# ESP_12.net
KiCad netlist of a schematic drawn in Altium Designer
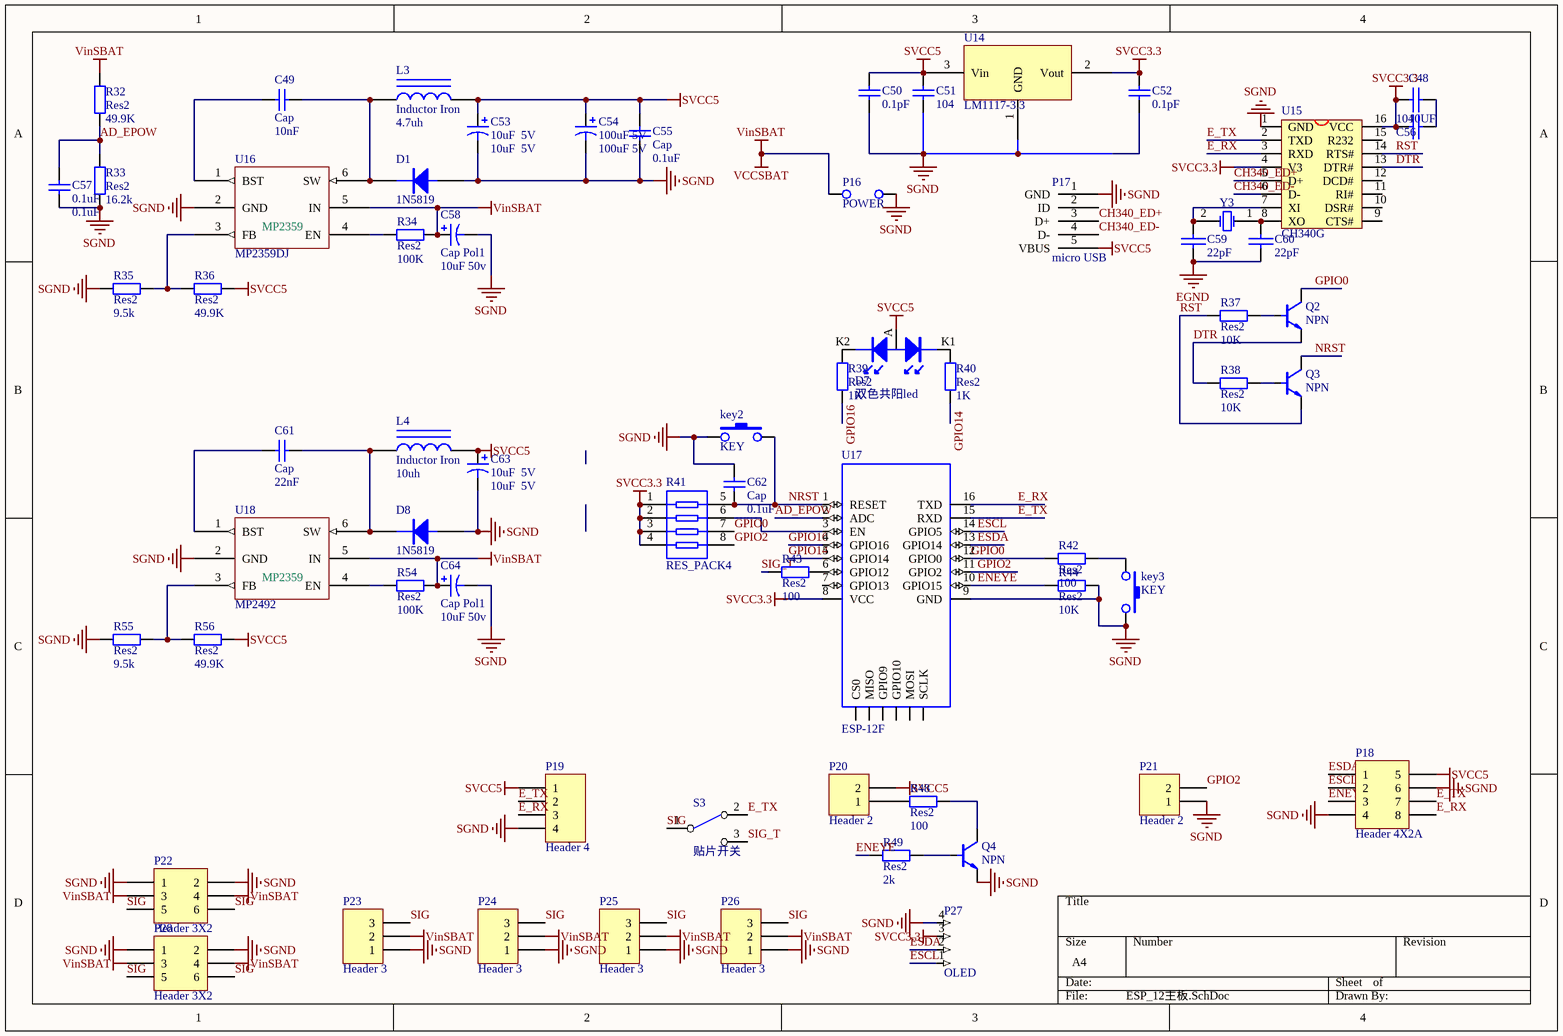
[diagram p0: ESP_12主板.SchDoc]

(export (version "E")
  (design (tool "Eeschema 10.0.6"))
  (components
    (comp (ref "C48")
      (value "10UF")
      (footprint "LC-0603_C")
      (fields (field (name "Comment") "CAP"))
      (libsource (lib "MySchLib") (part "CAP"))
    )
    (comp (ref "C49")
      (value "Cap")
      (footprint "LC-0603_C")
      (description "Capacitor")
      (fields (field (name "ALTIUM_VALUE") "10nF") (field (name "PUBLISHER") "Altium Limited"))
      (libsource (lib "Miscellaneous Devices") (part "Cap"))
    )
    (comp (ref "C50")
      (value "0.1pF")
      (footprint "LC-0603_C")
      (description "Capacitor")
      (fields (field (name "Comment") "Cap") (field (name "PUBLISHER") "Altium Limited"))
      (libsource (lib "Miscellaneous Devices") (part "Cap"))
    )
    (comp (ref "C51")
      (value "104")
      (footprint "LC-Standard-FootPrints-AD-V1.00:LC-1210_C")
      (description "Capacitor")
      (fields (field (name "Comment") "Cap") (field (name "PUBLISHER") "Altium Limited"))
      (libsource (lib "Miscellaneous Devices") (part "Cap"))
    )
    (comp (ref "C52")
      (value "0.1pF")
      (footprint "LC-0603_C")
      (description "Capacitor")
      (fields (field (name "Comment") "Cap") (field (name "PUBLISHER") "Altium Limited"))
      (libsource (lib "Miscellaneous Devices") (part "Cap"))
    )
    (comp (ref "C53")
      (value "10uF  5V")
      (footprint "LC-1210_C")
      (description "Polarized Capacitor (Radial)")
      (fields (field (name "ALTIUM_VALUE") "10uF  5V") (field (name "PUBLISHER") "Altium Limited"))
      (libsource (lib "Miscellaneous Devices") (part "Cap Pol1"))
    )
    (comp (ref "C54")
      (value "100uF 5V")
      (footprint "电容HONOR_63X77")
      (description "Polarized Capacitor (Radial)")
      (fields (field (name "ALTIUM_VALUE") "100uF 5V") (field (name "PUBLISHER") "Altium Limited"))
      (libsource (lib "Miscellaneous Devices") (part "Cap Pol1"))
    )
    (comp (ref "C55")
      (value "Cap")
      (footprint "LC-0603_C")
      (description "Capacitor")
      (fields (field (name "ALTIUM_VALUE") "0.1uF") (field (name "PUBLISHER") "Altium Limited"))
      (libsource (lib "Miscellaneous Devices") (part "Cap"))
    )
    (comp (ref "C56")
      (value "104")
      (footprint "LC-1206_C")
      (fields (field (name "Comment") "CAP"))
      (libsource (lib "MySchLib") (part "CAP"))
    )
    (comp (ref "C57")
      (value "0.1uF")
      (footprint "LC-0603_C")
      (description "Capacitor")
      (fields (field (name "ALTIUM_VALUE") "0.1uF") (field (name "PUBLISHER") "Altium Limited"))
      (libsource (lib "Miscellaneous Devices") (part "Cap"))
    )
    (comp (ref "C58")
      (value "Cap Pol1")
      (footprint "电容HONOR_63X54")
      (description "Polarized Capacitor (Radial)")
      (fields (field (name "ALTIUM_VALUE") "10uF 50v") (field (name "PUBLISHER") "Altium Limited"))
      (libsource (lib "Miscellaneous Devices") (part "Cap Pol1"))
    )
    (comp (ref "C59")
      (value "22pF")
      (footprint "LC-0603_C")
      (fields (field (name "Comment") "CAP"))
      (libsource (lib "MySchLib") (part "CAP"))
    )
    (comp (ref "C60")
      (value "22pF")
      (footprint "LC-0603_C")
      (fields (field (name "Comment") "CAP"))
      (libsource (lib "MySchLib") (part "CAP"))
    )
    (comp (ref "C61")
      (value "Cap")
      (footprint "LC-0603_C")
      (description "Capacitor")
      (fields (field (name "ALTIUM_VALUE") "22nF") (field (name "PUBLISHER") "Altium Limited"))
      (libsource (lib "Miscellaneous Devices") (part "Cap"))
    )
    (comp (ref "C62")
      (value "Cap")
      (footprint "LC-0603_C")
      (description "Capacitor")
      (fields (field (name "ALTIUM_VALUE") "0.1uF") (field (name "PUBLISHER") "Altium Limited"))
      (libsource (lib "Miscellaneous Devices") (part "Cap"))
    )
    (comp (ref "C63")
      (value "10uF  5V")
      (footprint "LC-1210_C")
      (description "Polarized Capacitor (Radial)")
      (fields (field (name "ALTIUM_VALUE") "10uF  5V") (field (name "PUBLISHER") "Altium Limited"))
      (libsource (lib "Miscellaneous Devices") (part "Cap Pol1"))
    )
    (comp (ref "C64")
      (value "Cap Pol1")
      (footprint "电容HONOR_63X54")
      (description "Polarized Capacitor (Radial)")
      (fields (field (name "ALTIUM_VALUE") "10uF 50v") (field (name "PUBLISHER") "Altium Limited"))
      (libsource (lib "Miscellaneous Devices") (part "Cap Pol1"))
    )
    (comp (ref "D1") (value "1N5819") (footprint "SMA") (libsource (lib "ARAMYLIB") (part "1N4001")))
    (comp (ref "D7") (value "双色共阳led") (footprint "共阳双色LED") (libsource (lib "ros_car_lib") (part "双色共阳led")))
    (comp (ref "D8") (value "1N5819") (footprint "SMA") (libsource (lib "ARAMYLIB") (part "1N4001")))
    (comp (ref "key2") (value "KEY") (footprint "SMD轻触按键") (libsource (lib "ros_car_lib") (part "KEY")))
    (comp (ref "key3") (value "KEY") (footprint "SMD轻触按键") (libsource (lib "ros_car_lib") (part "KEY")))
    (comp (ref "L3")
      (value "Inductor Iron")
      (footprint "电感GDCD4532")
      (description "Magnetic-Core Inductor")
      (fields (field (name "ALTIUM_VALUE") "4.7uh") (field (name "PUBLISHER") "Altium Limited"))
      (libsource (lib "Miscellaneous Devices") (part "Inductor Iron"))
    )
    (comp (ref "L4")
      (value "Inductor Iron")
      (footprint "电感GDCD4532")
      (description "Magnetic-Core Inductor")
      (fields (field (name "ALTIUM_VALUE") "10uh") (field (name "PUBLISHER") "Altium Limited"))
      (libsource (lib "Miscellaneous Devices") (part "Inductor Iron"))
    )
    (comp (ref "P16") (value "POWER") (footprint "电源") (libsource (lib "ROS_CAR_LIB") (part "POWER")))
    (comp (ref "P17")
      (value "micro USB")
      (footprint "micro 5P沉板式0.8四脚全插无导位有孔")
      (libsource (lib "ROS_CAR_LIB") (part "micro 5P"))
    )
    (comp (ref "P18")
      (value "Header 4X2A")
      (footprint "HDR2X4_CEN")
      (description "Header, 4-Pin, Dual row")
      (fields (field (name "PUBLISHER") "Altium Limited"))
      (libsource (lib "Miscellaneous Connectors") (part "Header 4X2A"))
    )
    (comp (ref "P19")
      (value "Header 4")
      (footprint "HDR1X4")
      (description "Header, 4-Pin")
      (fields (field (name "PUBLISHER") "Altium Limited"))
      (libsource (lib "Miscellaneous Connectors") (part "Header 4"))
    )
    (comp (ref "P20")
      (value "Header 2")
      (footprint "HDR1X2")
      (description "Header, 2-Pin")
      (fields (field (name "PUBLISHER") "Altium Limited"))
      (libsource (lib "Miscellaneous Connectors") (part "Header 2"))
    )
    (comp (ref "P21")
      (value "Header 2")
      (footprint "HDR1X2")
      (description "Header, 2-Pin")
      (fields (field (name "PUBLISHER") "Altium Limited"))
      (libsource (lib "Miscellaneous Connectors") (part "Header 2"))
    )
    (comp (ref "P22")
      (value "Header 3X2")
      (footprint "HDR2X3")
      (description "Header, 3-Pin, Dual row")
      (fields (field (name "PUBLISHER") "Altium Limited"))
      (libsource (lib "Miscellaneous Connectors") (part "Header 3X2"))
    )
    (comp (ref "P23")
      (value "Header 3")
      (footprint "AMP 3针连接件")
      (description "Header, 3-Pin")
      (fields (field (name "PUBLISHER") "Altium Limited"))
      (libsource (lib "Miscellaneous Connectors") (part "Header 3"))
    )
    (comp (ref "P24")
      (value "Header 3")
      (footprint "AMP 3针连接件")
      (description "Header, 3-Pin")
      (fields (field (name "PUBLISHER") "Altium Limited"))
      (libsource (lib "Miscellaneous Connectors") (part "Header 3"))
    )
    (comp (ref "P25")
      (value "Header 3")
      (footprint "AMP 3针连接件")
      (description "Header, 3-Pin")
      (fields (field (name "PUBLISHER") "Altium Limited"))
      (libsource (lib "Miscellaneous Connectors") (part "Header 3"))
    )
    (comp (ref "P26")
      (value "Header 3")
      (footprint "AMP 3针连接件")
      (description "Header, 3-Pin")
      (fields (field (name "PUBLISHER") "Altium Limited"))
      (libsource (lib "Miscellaneous Connectors") (part "Header 3"))
    )
    (comp (ref "P27")
      (value "OLED")
      (footprint "1.0MM 翻盖 下接 FPC连接器 4P")
      (libsource (lib "ros_car_lib") (part "FPC 4P 1MM"))
    )
    (comp (ref "P28")
      (value "Header 3X2")
      (footprint "HDR2X3")
      (description "Header, 3-Pin, Dual row")
      (fields (field (name "PUBLISHER") "Altium Limited"))
      (libsource (lib "Miscellaneous Connectors") (part "Header 3X2"))
    )
    (comp (ref "Q2") (value "NPN") (footprint "LC-SOT-23") (libsource (lib "ARAMYLIB") (part "NPN")))
    (comp (ref "Q3") (value "NPN") (footprint "LC-SOT-23") (libsource (lib "ARAMYLIB") (part "NPN")))
    (comp (ref "Q4") (value "NPN") (footprint "LC-SOT-23") (libsource (lib "ARAMYLIB") (part "NPN")))
    (comp (ref "R32")
      (value "Res2")
      (footprint "LC-0603_R")
      (description "Resistor")
      (fields (field (name "ALTIUM_VALUE") "49.9K") (field (name "PUBLISHER") "Altium Limited"))
      (libsource (lib "") (part "Res2_2"))
    )
    (comp (ref "R33")
      (value "Res2")
      (footprint "LC-0603_R")
      (description "Resistor")
      (fields (field (name "ALTIUM_VALUE") "16.2k") (field (name "PUBLISHER") "Altium Limited"))
      (libsource (lib "") (part "Res2_2"))
    )
    (comp (ref "R34")
      (value "Res2")
      (footprint "LC-0603_R")
      (description "Resistor")
      (fields (field (name "ALTIUM_VALUE") "100K") (field (name "PUBLISHER") "Altium Limited"))
      (libsource (lib "") (part "Res2_1"))
    )
    (comp (ref "R35")
      (value "Res2")
      (footprint "LC-0603_R")
      (description "Resistor")
      (fields (field (name "ALTIUM_VALUE") "9.5k") (field (name "PUBLISHER") "Altium Limited"))
      (libsource (lib "Miscellaneous Devices") (part "Res2"))
    )
    (comp (ref "R36")
      (value "Res2")
      (footprint "LC-0603_R")
      (description "Resistor")
      (fields (field (name "ALTIUM_VALUE") "49.9K") (field (name "PUBLISHER") "Altium Limited"))
      (libsource (lib "Miscellaneous Devices") (part "Res2"))
    )
    (comp (ref "R37")
      (value "Res2")
      (footprint "LC-0603_R")
      (description "Resistor")
      (fields (field (name "ALTIUM_VALUE") "10K") (field (name "PUBLISHER") "Altium Limited"))
      (libsource (lib "") (part "Res2_1"))
    )
    (comp (ref "R38")
      (value "Res2")
      (footprint "LC-0603_R")
      (description "Resistor")
      (fields (field (name "ALTIUM_VALUE") "10K") (field (name "PUBLISHER") "Altium Limited"))
      (libsource (lib "") (part "Res2_1"))
    )
    (comp (ref "R39")
      (value "Res2")
      (footprint "LC-0603_R")
      (description "Resistor")
      (fields (field (name "ALTIUM_VALUE") "1K") (field (name "PUBLISHER") "Altium Limited"))
      (libsource (lib "") (part "Res2_3"))
    )
    (comp (ref "R40")
      (value "Res2")
      (footprint "LC-0603_R")
      (description "Resistor")
      (fields (field (name "ALTIUM_VALUE") "1K") (field (name "PUBLISHER") "Altium Limited"))
      (libsource (lib "") (part "Res2_3"))
    )
    (comp (ref "R41") (value "RES_PACK4") (footprint "RES4") (libsource (lib "ARAMYLIB") (part "RES_PACK4")))
    (comp (ref "R42")
      (value "Res2")
      (footprint "LC-0603_R")
      (description "Resistor")
      (fields (field (name "ALTIUM_VALUE") "100") (field (name "PUBLISHER") "Altium Limited"))
      (libsource (lib "") (part "Res2_1"))
    )
    (comp (ref "R43")
      (value "Res2")
      (footprint "LC-0603_R")
      (description "Resistor")
      (fields (field (name "ALTIUM_VALUE") "100") (field (name "PUBLISHER") "Altium Limited"))
      (libsource (lib "") (part "Res2_1"))
    )
    (comp (ref "R44")
      (value "Res2")
      (footprint "LC-0603_R")
      (description "Resistor")
      (fields (field (name "ALTIUM_VALUE") "10K") (field (name "PUBLISHER") "Altium Limited"))
      (libsource (lib "") (part "Res2_1"))
    )
    (comp (ref "R48")
      (value "Res2")
      (footprint "LC-0603_R")
      (description "Resistor")
      (fields (field (name "ALTIUM_VALUE") "100") (field (name "PUBLISHER") "Altium Limited"))
      (libsource (lib "") (part "Res2_1"))
    )
    (comp (ref "R49")
      (value "Res2")
      (footprint "LC-0603_R")
      (description "Resistor")
      (fields (field (name "ALTIUM_VALUE") "2k") (field (name "PUBLISHER") "Altium Limited"))
      (libsource (lib "Miscellaneous Devices") (part "Res2"))
    )
    (comp (ref "R54")
      (value "Res2")
      (footprint "LC-0603_R")
      (description "Resistor")
      (fields (field (name "ALTIUM_VALUE") "100K") (field (name "PUBLISHER") "Altium Limited"))
      (libsource (lib "") (part "Res2_1"))
    )
    (comp (ref "R55")
      (value "Res2")
      (footprint "LC-0603_R")
      (description "Resistor")
      (fields (field (name "ALTIUM_VALUE") "9.5k") (field (name "PUBLISHER") "Altium Limited"))
      (libsource (lib "Miscellaneous Devices") (part "Res2"))
    )
    (comp (ref "R56")
      (value "Res2")
      (footprint "LC-0603_R")
      (description "Resistor")
      (fields (field (name "ALTIUM_VALUE") "49.9K") (field (name "PUBLISHER") "Altium Limited"))
      (libsource (lib "Miscellaneous Devices") (part "Res2"))
    )
    (comp (ref "S3") (value "贴片开关") (footprint "KEY") (libsource (lib "aramy_四轴") (part "贴片开关")))
    (comp (ref "U14")
      (value "LM1117-3.3")
      (footprint "SOT223")
      (libsource (lib "MySchLib") (part "LM1117-3.3"))
    )
    (comp (ref "U15")
      (value "CH340G")
      (footprint "SOP16M")
      (description "USB2UART")
      (libsource (lib "EliteSTM32封装库") (part "CH340G"))
    )
    (comp (ref "U16")
      (value "MP2359DJ")
      (footprint "LC-SOT-23-6")
      (libsource (lib "ARAMYLIB") (part "MP2359DJ"))
    )
    (comp (ref "U17") (value "ESP-12F") (footprint "ESP_12") (libsource (lib "ros_car_lib") (part "ESP-12F")))
    (comp (ref "U18")
      (value "MP2492")
      (footprint "LC-SOT-23-6")
      (libsource (lib "ARAMYLIB") (part "MP2359DJ"))
    )
    (comp (ref "Y3")
      (value "12MHz")
      (footprint "49SMD")
      (description "Crystal Oscillator")
      (fields (field (name "PUBLISHER") "Altium Limited"))
      (libsource (lib "ALIENTEK_底板封装库") (part "XTAL"))
    )
  )
  (nets
    (net (code "1") (name "/AD_EPOW") (class "Default")
      (node (ref "C57") (pin "1") (pinfunction "1_1") (pintype "passive"))
      (node (ref "R32") (pin "2") (pinfunction "2_2") (pintype "passive"))
      (node (ref "R33") (pin "1") (pinfunction "1_1") (pintype "passive"))
      (node (ref "U17") (pin "2") (pinfunction "ADC_2") (pintype "bidirectional"))
    )
    (net (code "2") (name "/CH340_ED+") (class "Default")
      (node (ref "P17") (pin "3") (pinfunction "D+_3") (pintype "passive"))
      (node (ref "U15") (pin "5") (pinfunction "D+_5") (pintype "passive"))
    )
    (net (code "3") (name "/CH340_ED-") (class "Default")
      (node (ref "P17") (pin "4") (pinfunction "D-_4") (pintype "passive"))
      (node (ref "U15") (pin "6") (pinfunction "D-_6") (pintype "passive"))
    )
    (net (code "4") (name "/DTR") (class "Default")
      (node (ref "Q2") (pin "E") (pinfunction "e_E") (pintype "passive"))
      (node (ref "R38") (pin "1") (pinfunction "1_1") (pintype "passive"))
      (node (ref "U15") (pin "13") (pinfunction "DTR#_13") (pintype "passive"))
    )
    (net (code "5") (name "/ENEYE") (class "Default")
      (node (ref "P18") (pin "3") (pinfunction "3_3") (pintype "passive"))
      (node (ref "R44") (pin "1") (pinfunction "1_1") (pintype "passive"))
      (node (ref "R49") (pin "2") (pinfunction "2_2") (pintype "passive"))
      (node (ref "U17") (pin "10") (pinfunction "GPIO15_10") (pintype "bidirectional"))
    )
    (net (code "6") (name "/ESCL") (class "Default")
      (node (ref "P18") (pin "2") (pinfunction "2_2") (pintype "passive"))
      (node (ref "P27") (pin "1") (pinfunction "1_1") (pintype "input"))
      (node (ref "U17") (pin "14") (pinfunction "GPIO5_14") (pintype "bidirectional"))
    )
    (net (code "7") (name "/ESDA") (class "Default")
      (node (ref "P18") (pin "1") (pinfunction "1_1") (pintype "passive"))
      (node (ref "P27") (pin "2") (pinfunction "2_2") (pintype "input"))
      (node (ref "U17") (pin "13") (pinfunction "GPIO14_13") (pintype "bidirectional"))
    )
    (net (code "8") (name "/E_RX") (class "Default")
      (node (ref "P18") (pin "8") (pinfunction "8_8") (pintype "passive"))
      (node (ref "P19") (pin "3") (pinfunction "3_3") (pintype "passive"))
      (node (ref "U15") (pin "3") (pinfunction "RXD_3") (pintype "passive"))
      (node (ref "U17") (pin "16") (pinfunction "TXD_16") (pintype "passive"))
    )
    (net (code "9") (name "/E_TX") (class "Default")
      (node (ref "P18") (pin "7") (pinfunction "7_7") (pintype "passive"))
      (node (ref "P19") (pin "2") (pinfunction "2_2") (pintype "passive"))
      (node (ref "S3") (pin "2") (pinfunction "NC1_2") (pintype "passive"))
      (node (ref "U15") (pin "2") (pinfunction "TXD_2") (pintype "passive"))
      (node (ref "U17") (pin "15") (pinfunction "RXD_15") (pintype "passive"))
    )
    (net (code "10") (name "/GPIO0") (class "Default")
      (node (ref "Q2") (pin "C") (pinfunction "c_C") (pintype "passive"))
      (node (ref "R41") (pin "7") (pinfunction "7_7") (pintype "passive"))
      (node (ref "R42") (pin "1") (pinfunction "1_1") (pintype "passive"))
      (node (ref "U17") (pin "12") (pinfunction "GPIO0_12") (pintype "bidirectional"))
    )
    (net (code "11") (name "/GPIO2") (class "Default")
      (node (ref "P21") (pin "2") (pinfunction "2_2") (pintype "passive"))
      (node (ref "R41") (pin "8") (pinfunction "8_8") (pintype "passive"))
      (node (ref "U17") (pin "11") (pinfunction "GPIO2_11") (pintype "bidirectional"))
    )
    (net (code "12") (name "/GPIO14") (class "Default")
      (node (ref "R40") (pin "1") (pinfunction "1_1") (pintype "passive"))
      (node (ref "U17") (pin "5") (pinfunction "GPIO14_5") (pintype "bidirectional"))
    )
    (net (code "13") (name "/GPIO16") (class "Default")
      (node (ref "R39") (pin "1") (pinfunction "1_1") (pintype "passive"))
      (node (ref "U17") (pin "4") (pinfunction "GPIO16_4") (pintype "bidirectional"))
    )
    (net (code "14") (name "/NRST") (class "Default")
      (node (ref "C62") (pin "1") (pinfunction "1_1") (pintype "passive"))
      (node (ref "Q3") (pin "C") (pinfunction "c_C") (pintype "passive"))
      (node (ref "R41") (pin "5") (pinfunction "5_5") (pintype "passive"))
      (node (ref "U17") (pin "1") (pinfunction "RESET_1") (pintype "bidirectional"))
      (node (ref "key2") (pin "2") (pinfunction "2_2") (pintype "passive"))
    )
    (net (code "15") (name "/RST") (class "Default")
      (node (ref "Q3") (pin "E") (pinfunction "e_E") (pintype "passive"))
      (node (ref "R37") (pin "1") (pinfunction "1_1") (pintype "passive"))
      (node (ref "U15") (pin "14") (pinfunction "RTS#_14") (pintype "passive"))
    )
    (net (code "16") (name "/SIG") (class "Default")
      (node (ref "P22") (pin "5") (pinfunction "5_5") (pintype "passive"))
      (node (ref "P22") (pin "6") (pinfunction "6_6") (pintype "passive"))
      (node (ref "P23") (pin "3") (pinfunction "3_3") (pintype "passive"))
      (node (ref "P24") (pin "3") (pinfunction "3_3") (pintype "passive"))
      (node (ref "P25") (pin "3") (pinfunction "3_3") (pintype "passive"))
      (node (ref "P26") (pin "3") (pinfunction "3_3") (pintype "passive"))
      (node (ref "P28") (pin "5") (pinfunction "5_5") (pintype "passive"))
      (node (ref "P28") (pin "6") (pinfunction "6_6") (pintype "passive"))
      (node (ref "S3") (pin "1") (pinfunction "COMMON1_1") (pintype "passive"))
    )
    (net (code "17") (name "/SIG_T") (class "Default")
      (node (ref "R43") (pin "1") (pinfunction "1_1") (pintype "passive"))
      (node (ref "S3") (pin "3") (pinfunction "NO1_3") (pintype "passive"))
    )
    (net (code "18") (name "EGND") (class "Default")
      (node (ref "C59") (pin "1") (pinfunction "1_1") (pintype "passive"))
      (node (ref "C60") (pin "1") (pinfunction "1_1") (pintype "passive"))
    )
    (net (code "19") (name "Net-(C48-Pad1)") (class "Default")
      (node (ref "C48") (pin "1") (pinfunction "1_1") (pintype "passive"))
      (node (ref "C56") (pin "2") (pinfunction "2_2") (pintype "passive"))
    )
    (net (code "20") (name "Net-(D1-2)") (class "Default")
      (node (ref "C49") (pin "2") (pinfunction "2_2") (pintype "passive"))
      (node (ref "D1") (pin "K") (pinfunction "2_K") (pintype "passive"))
      (node (ref "L3") (pin "1") (pinfunction "1_1") (pintype "passive"))
      (node (ref "U16") (pin "6") (pinfunction "SW_6") (pintype "input"))
    )
    (net (code "21") (name "Net-(D7-1)") (class "Default")
      (node (ref "D7") (pin "K1") (pinfunction "1_K1") (pintype "passive"))
      (node (ref "R40") (pin "2") (pinfunction "2_2") (pintype "passive"))
    )
    (net (code "22") (name "Net-(D7-3)") (class "Default")
      (node (ref "D7") (pin "K2") (pinfunction "3_K2") (pintype "passive"))
      (node (ref "R39") (pin "2") (pinfunction "2_2") (pintype "passive"))
    )
    (net (code "23") (name "Net-(D8-2)") (class "Default")
      (node (ref "C61") (pin "2") (pinfunction "2_2") (pintype "passive"))
      (node (ref "D8") (pin "K") (pinfunction "2_K") (pintype "passive"))
      (node (ref "L4") (pin "1") (pinfunction "1_1") (pintype "passive"))
      (node (ref "U18") (pin "6") (pinfunction "SW_6") (pintype "input"))
    )
    (net (code "24") (name "Net-(P20-Pad1)") (class "Default")
      (node (ref "P20") (pin "1") (pinfunction "1_1") (pintype "passive"))
      (node (ref "R48") (pin "1") (pinfunction "1_1") (pintype "passive"))
    )
    (net (code "25") (name "Net-(Q2-b)") (class "Default")
      (node (ref "Q2") (pin "B") (pinfunction "b_B") (pintype "passive"))
      (node (ref "R37") (pin "2") (pinfunction "2_2") (pintype "passive"))
    )
    (net (code "26") (name "Net-(Q3-b)") (class "Default")
      (node (ref "Q3") (pin "B") (pinfunction "b_B") (pintype "passive"))
      (node (ref "R38") (pin "2") (pinfunction "2_2") (pintype "passive"))
    )
    (net (code "27") (name "Net-(Q4-b)") (class "Default")
      (node (ref "Q4") (pin "B") (pinfunction "b_B") (pintype "passive"))
      (node (ref "R49") (pin "1") (pinfunction "1_1") (pintype "passive"))
    )
    (net (code "28") (name "Net-(Q4-c)") (class "Default")
      (node (ref "Q4") (pin "C") (pinfunction "c_C") (pintype "passive"))
      (node (ref "R48") (pin "2") (pinfunction "2_2") (pintype "passive"))
    )
    (net (code "29") (name "Net-(R42-Pad2)") (class "Default")
      (node (ref "R42") (pin "2") (pinfunction "2_2") (pintype "passive"))
      (node (ref "key3") (pin "1") (pinfunction "1_1") (pintype "passive"))
    )
    (net (code "30") (name "Net-(U15-XI)") (class "Default")
      (node (ref "C59") (pin "2") (pinfunction "2_2") (pintype "passive"))
      (node (ref "U15") (pin "7") (pinfunction "XI_7") (pintype "passive"))
      (node (ref "Y3") (pin "2") (pinfunction "OSC2_2") (pintype "passive"))
    )
    (net (code "31") (name "Net-(U15-XO)") (class "Default")
      (node (ref "C60") (pin "2") (pinfunction "2_2") (pintype "passive"))
      (node (ref "U15") (pin "8") (pinfunction "XO_8") (pintype "passive"))
      (node (ref "Y3") (pin "1") (pinfunction "OSC1_1") (pintype "passive"))
    )
    (net (code "32") (name "Net-(U16-BST)") (class "Default")
      (node (ref "C49") (pin "1") (pinfunction "1_1") (pintype "passive"))
      (node (ref "U16") (pin "1") (pinfunction "BST_1") (pintype "output"))
    )
    (net (code "33") (name "Net-(U16-EN)") (class "Default")
      (node (ref "R34") (pin "1") (pinfunction "1_1") (pintype "passive"))
      (node (ref "U16") (pin "4") (pinfunction "EN_4") (pintype "power_in"))
    )
    (net (code "34") (name "Net-(U16-FB)") (class "Default")
      (node (ref "R35") (pin "1") (pinfunction "1_1") (pintype "passive"))
      (node (ref "R36") (pin "2") (pinfunction "2_2") (pintype "passive"))
      (node (ref "U16") (pin "3") (pinfunction "FB_3") (pintype "output"))
    )
    (net (code "35") (name "Net-(U17-EN)") (class "Default")
      (node (ref "R41") (pin "6") (pinfunction "6_6") (pintype "passive"))
      (node (ref "U17") (pin "3") (pinfunction "EN_3") (pintype "bidirectional"))
    )
    (net (code "36") (name "Net-(U17-GPIO12)") (class "Default")
      (node (ref "R43") (pin "2") (pinfunction "2_2") (pintype "passive"))
      (node (ref "U17") (pin "6") (pinfunction "GPIO12_6") (pintype "bidirectional"))
    )
    (net (code "37") (name "Net-(U18-BST)") (class "Default")
      (node (ref "C61") (pin "1") (pinfunction "1_1") (pintype "passive"))
      (node (ref "U18") (pin "1") (pinfunction "BST_1") (pintype "output"))
    )
    (net (code "38") (name "Net-(U18-EN)") (class "Default")
      (node (ref "R54") (pin "1") (pinfunction "1_1") (pintype "passive"))
      (node (ref "U18") (pin "4") (pinfunction "EN_4") (pintype "power_in"))
    )
    (net (code "39") (name "Net-(U18-FB)") (class "Default")
      (node (ref "R55") (pin "1") (pinfunction "1_1") (pintype "passive"))
      (node (ref "R56") (pin "2") (pinfunction "2_2") (pintype "passive"))
      (node (ref "U18") (pin "3") (pinfunction "FB_3") (pintype "output"))
    )
    (net (code "40") (name "SGND") (class "Default")
      (node (ref "C50") (pin "2") (pinfunction "2_2") (pintype "passive"))
      (node (ref "C51") (pin "1") (pinfunction "1_1") (pintype "passive"))
      (node (ref "C52") (pin "2") (pinfunction "2_2") (pintype "passive"))
      (node (ref "C53") (pin "2") (pinfunction "2_2") (pintype "passive"))
      (node (ref "C54") (pin "2") (pinfunction "2_2") (pintype "passive"))
      (node (ref "C55") (pin "1") (pinfunction "1_1") (pintype "passive"))
      (node (ref "C57") (pin "2") (pinfunction "2_2") (pintype "passive"))
      (node (ref "C58") (pin "2") (pinfunction "2_2") (pintype "passive"))
      (node (ref "C62") (pin "2") (pinfunction "2_2") (pintype "passive"))
      (node (ref "C63") (pin "2") (pinfunction "2_2") (pintype "passive"))
      (node (ref "C64") (pin "2") (pinfunction "2_2") (pintype "passive"))
      (node (ref "D1") (pin "A") (pinfunction "1_A") (pintype "passive"))
      (node (ref "D8") (pin "A") (pinfunction "1_A") (pintype "passive"))
      (node (ref "P16") (pin "2") (pinfunction "2_2") (pintype "passive"))
      (node (ref "P17") (pin "1") (pinfunction "GND_1") (pintype "power_in"))
      (node (ref "P18") (pin "4") (pinfunction "4_4") (pintype "passive"))
      (node (ref "P18") (pin "6") (pinfunction "6_6") (pintype "passive"))
      (node (ref "P19") (pin "4") (pinfunction "4_4") (pintype "passive"))
      (node (ref "P21") (pin "1") (pinfunction "1_1") (pintype "passive"))
      (node (ref "P22") (pin "1") (pinfunction "1_1") (pintype "passive"))
      (node (ref "P22") (pin "2") (pinfunction "2_2") (pintype "passive"))
      (node (ref "P23") (pin "1") (pinfunction "1_1") (pintype "passive"))
      (node (ref "P24") (pin "1") (pinfunction "1_1") (pintype "passive"))
      (node (ref "P25") (pin "1") (pinfunction "1_1") (pintype "passive"))
      (node (ref "P26") (pin "1") (pinfunction "1_1") (pintype "passive"))
      (node (ref "P27") (pin "4") (pinfunction "4_4") (pintype "input"))
      (node (ref "P28") (pin "1") (pinfunction "1_1") (pintype "passive"))
      (node (ref "P28") (pin "2") (pinfunction "2_2") (pintype "passive"))
      (node (ref "Q4") (pin "E") (pinfunction "e_E") (pintype "passive"))
      (node (ref "R33") (pin "2") (pinfunction "2_2") (pintype "passive"))
      (node (ref "R35") (pin "2") (pinfunction "2_2") (pintype "passive"))
      (node (ref "R44") (pin "2") (pinfunction "2_2") (pintype "passive"))
      (node (ref "R55") (pin "2") (pinfunction "2_2") (pintype "passive"))
      (node (ref "U14") (pin "1") (pinfunction "GND_1") (pintype "passive"))
      (node (ref "U15") (pin "1") (pinfunction "GND_1") (pintype "passive"))
      (node (ref "U16") (pin "2") (pinfunction "GND_2") (pintype "power_in"))
      (node (ref "U17") (pin "9") (pinfunction "GND_9") (pintype "power_in"))
      (node (ref "U18") (pin "2") (pinfunction "GND_2") (pintype "power_in"))
      (node (ref "key2") (pin "1") (pinfunction "1_1") (pintype "passive"))
      (node (ref "key3") (pin "2") (pinfunction "2_2") (pintype "passive"))
    )
    (net (code "41") (name "SVCC3.3") (class "Default")
      (node (ref "C48") (pin "2") (pinfunction "2_2") (pintype "passive"))
      (node (ref "C52") (pin "1") (pinfunction "1_1") (pintype "passive"))
      (node (ref "C56") (pin "1") (pinfunction "1_1") (pintype "passive"))
      (node (ref "P27") (pin "3") (pinfunction "3_3") (pintype "input"))
      (node (ref "R41") (pin "1") (pinfunction "1_1") (pintype "passive"))
      (node (ref "R41") (pin "2") (pinfunction "2_2") (pintype "passive"))
      (node (ref "R41") (pin "3") (pinfunction "3_3") (pintype "passive"))
      (node (ref "R41") (pin "4") (pinfunction "4_4") (pintype "passive"))
      (node (ref "U14") (pin "2") (pinfunction "Vout_2") (pintype "passive"))
      (node (ref "U15") (pin "16") (pinfunction "VCC_16") (pintype "passive"))
      (node (ref "U15") (pin "4") (pinfunction "V3_4") (pintype "passive"))
      (node (ref "U17") (pin "8") (pinfunction "VCC_8") (pintype "power_in"))
    )
    (net (code "42") (name "SVCC5") (class "Default")
      (node (ref "C50") (pin "1") (pinfunction "1_1") (pintype "passive"))
      (node (ref "C51") (pin "2") (pinfunction "2_2") (pintype "passive"))
      (node (ref "C53") (pin "1") (pinfunction "1_1") (pintype "passive"))
      (node (ref "C54") (pin "1") (pinfunction "1_1") (pintype "passive"))
      (node (ref "C55") (pin "2") (pinfunction "2_2") (pintype "passive"))
      (node (ref "C63") (pin "1") (pinfunction "1_1") (pintype "passive"))
      (node (ref "D7") (pin "A") (pinfunction "2_A") (pintype "passive"))
      (node (ref "L3") (pin "2") (pinfunction "2_2") (pintype "passive"))
      (node (ref "L4") (pin "2") (pinfunction "2_2") (pintype "passive"))
      (node (ref "P17") (pin "5") (pinfunction "VBUS_5") (pintype "passive"))
      (node (ref "P18") (pin "5") (pinfunction "5_5") (pintype "passive"))
      (node (ref "P19") (pin "1") (pinfunction "1_1") (pintype "passive"))
      (node (ref "P20") (pin "2") (pinfunction "2_2") (pintype "passive"))
      (node (ref "R36") (pin "1") (pinfunction "1_1") (pintype "passive"))
      (node (ref "R56") (pin "1") (pinfunction "1_1") (pintype "passive"))
      (node (ref "U14") (pin "3") (pinfunction "Vin_3") (pintype "passive"))
    )
    (net (code "43") (name "VCCSBAT") (class "Default")
      (node (ref "C58") (pin "1") (pinfunction "1_1") (pintype "passive"))
      (node (ref "C64") (pin "1") (pinfunction "1_1") (pintype "passive"))
      (node (ref "P16") (pin "1") (pinfunction "1_1") (pintype "passive"))
      (node (ref "P22") (pin "3") (pinfunction "3_3") (pintype "passive"))
      (node (ref "P22") (pin "4") (pinfunction "4_4") (pintype "passive"))
      (node (ref "P23") (pin "2") (pinfunction "2_2") (pintype "passive"))
      (node (ref "P24") (pin "2") (pinfunction "2_2") (pintype "passive"))
      (node (ref "P25") (pin "2") (pinfunction "2_2") (pintype "passive"))
      (node (ref "P26") (pin "2") (pinfunction "2_2") (pintype "passive"))
      (node (ref "P28") (pin "3") (pinfunction "3_3") (pintype "passive"))
      (node (ref "P28") (pin "4") (pinfunction "4_4") (pintype "passive"))
      (node (ref "R32") (pin "1") (pinfunction "1_1") (pintype "passive"))
      (node (ref "R34") (pin "2") (pinfunction "2_2") (pintype "passive"))
      (node (ref "R54") (pin "2") (pinfunction "2_2") (pintype "passive"))
      (node (ref "U16") (pin "5") (pinfunction "IN_5") (pintype "power_in"))
      (node (ref "U18") (pin "5") (pinfunction "IN_5") (pintype "power_in"))
    )
    (net (code "44") (name "unconnected-(P17-ID-Pad2)") (class "Default")
      (node (ref "P17") (pin "2") (pinfunction "ID_2") (pintype "passive"))
    )
    (net (code "45") (name "unconnected-(U15-CTS#-Pad9)") (class "Default")
      (node (ref "U15") (pin "9") (pinfunction "CTS#_9") (pintype "passive"))
    )
    (net (code "46") (name "unconnected-(U15-DCD#-Pad12)") (class "Default")
      (node (ref "U15") (pin "12") (pinfunction "DCD#_12") (pintype "passive"))
    )
    (net (code "47") (name "unconnected-(U15-DSR#-Pad10)") (class "Default")
      (node (ref "U15") (pin "10") (pinfunction "DSR#_10") (pintype "passive"))
    )
    (net (code "48") (name "unconnected-(U15-R232-Pad15)") (class "Default")
      (node (ref "U15") (pin "15") (pinfunction "R232_15") (pintype "passive"))
    )
    (net (code "49") (name "unconnected-(U15-RI#-Pad11)") (class "Default")
      (node (ref "U15") (pin "11") (pinfunction "RI#_11") (pintype "passive"))
    )
    (net (code "50") (name "unconnected-(U17-CS0-Pad17)") (class "Default")
      (node (ref "U17") (pin "17") (pinfunction "CS0_17") (pintype "passive"))
    )
    (net (code "51") (name "unconnected-(U17-GPIO9-Pad19)") (class "Default")
      (node (ref "U17") (pin "19") (pinfunction "GPIO9_19") (pintype "passive"))
    )
    (net (code "52") (name "unconnected-(U17-GPIO10-Pad20)") (class "Default")
      (node (ref "U17") (pin "20") (pinfunction "GPIO10_20") (pintype "passive"))
    )
    (net (code "53") (name "unconnected-(U17-GPIO13-Pad7)") (class "Default")
      (node (ref "U17") (pin "7") (pinfunction "GPIO13_7") (pintype "bidirectional"))
    )
    (net (code "54") (name "unconnected-(U17-MISO-Pad18)") (class "Default")
      (node (ref "U17") (pin "18") (pinfunction "MISO_18") (pintype "passive"))
    )
    (net (code "55") (name "unconnected-(U17-MOSI-Pad21)") (class "Default")
      (node (ref "U17") (pin "21") (pinfunction "MOSI_21") (pintype "passive"))
    )
    (net (code "56") (name "unconnected-(U17-SCLK-Pad22)") (class "Default")
      (node (ref "U17") (pin "22") (pinfunction "SCLK_22") (pintype "passive"))
    )
  )
)
